# SCH_555-Circut_2025-10-18.net
KiCad netlist of a schematic drawn in EasyEDA
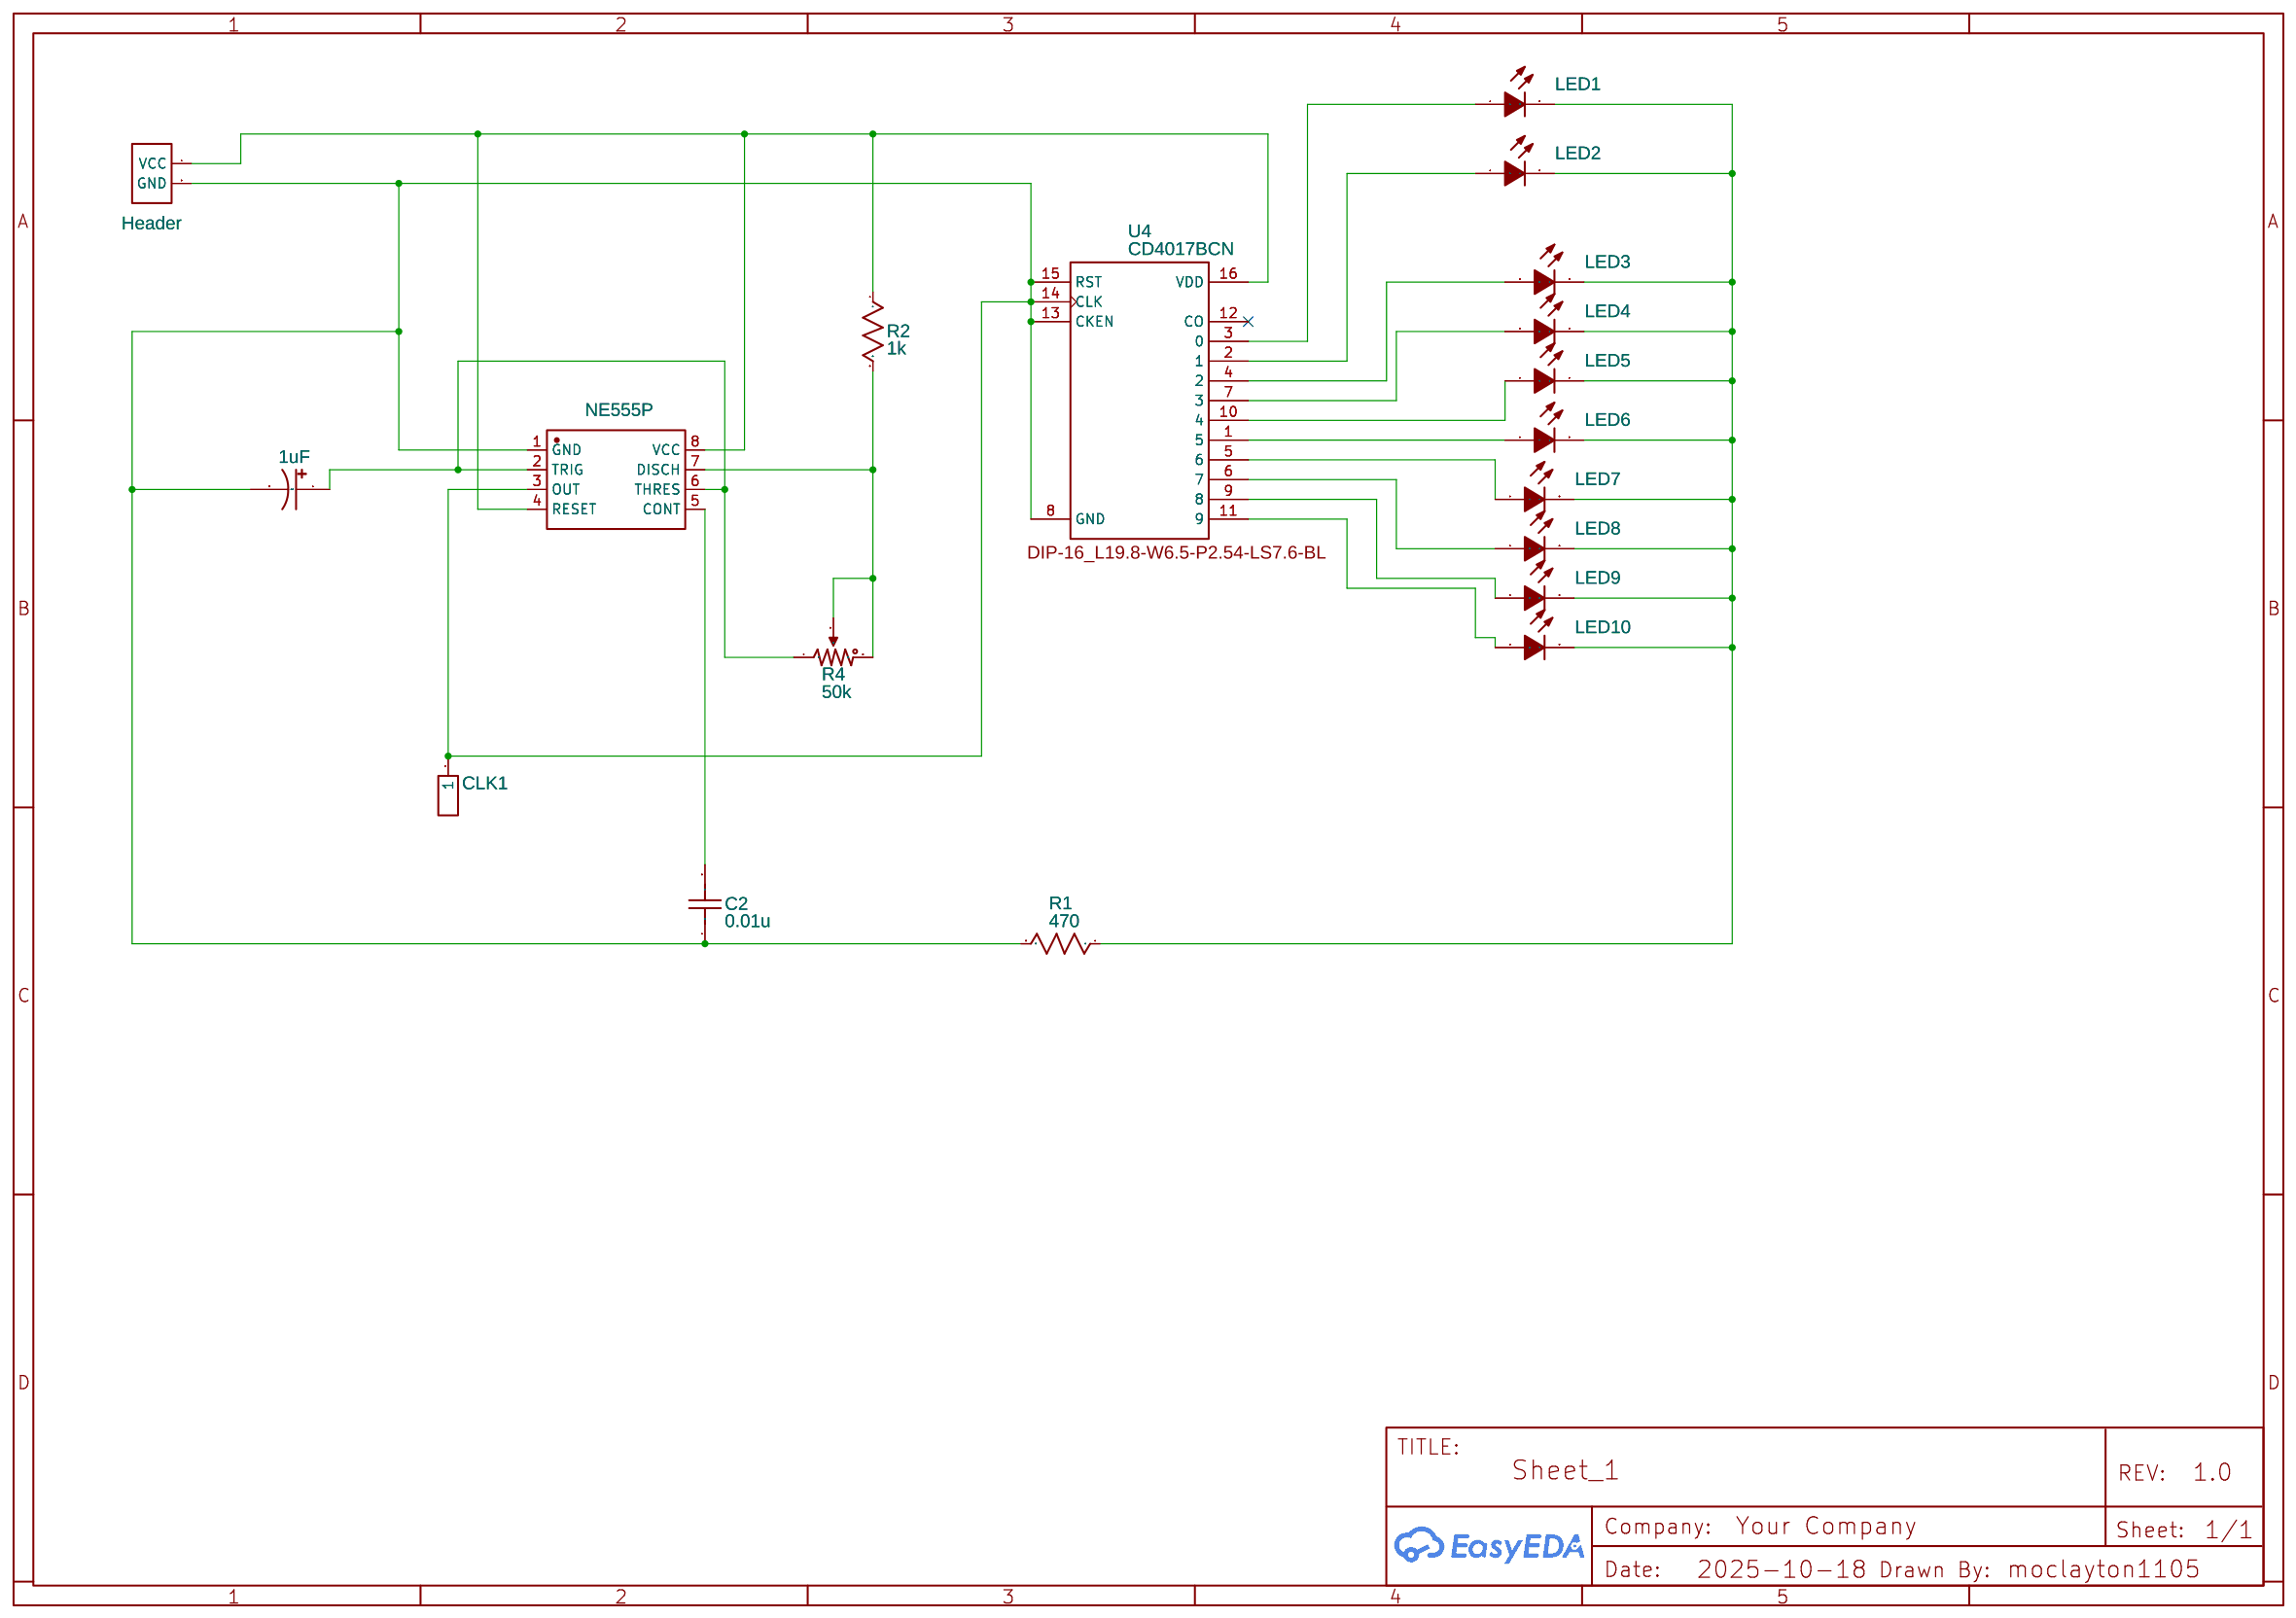
[diagram p0: schematic sheet]

(export (version "E")
  (design (tool "Eeschema 10.0.6"))
  (components
    (comp (ref "C1")
      (value "1uF")
      (fields (field (name "Manufacturer Part") "UVZ1H010MDD") (field (name "Manufacturer") "Nichicon(尼吉康)"))
      (libsource (lib "") (part "UVZ1H010MDD"))
    )
    (comp (ref "C2") (value "0.01u") (libsource (lib "") (part "C_0603_US")))
    (comp (ref "CLK1")
      (value "C81276")
      (fields
        (field (name "Manufacturer Part") "2.54-1*1P针")
        (field (name "Manufacturer") "BOOMELE(Boom Precision Elec)")
      )
      (libsource (lib "") (part "Header-Male-2.54_1x1"))
    )
    (comp (ref "H1") (value "Header") (libsource (lib "") (part "HEADER-FEMALE-2.54_1X2")))
    (comp (ref "LED1") (value "LED_5MM") (libsource (lib "") (part "LED_5MM")))
    (comp (ref "LED2") (value "LED_5MM") (libsource (lib "") (part "LED_5MM")))
    (comp (ref "LED3") (value "LED_5MM") (libsource (lib "") (part "LED_5MM")))
    (comp (ref "LED4") (value "LED_5MM") (libsource (lib "") (part "LED_5MM")))
    (comp (ref "LED5") (value "LED_5MM") (libsource (lib "") (part "LED_5MM")))
    (comp (ref "LED6") (value "LED_5MM") (libsource (lib "") (part "LED_5MM")))
    (comp (ref "LED7") (value "LED_5MM") (libsource (lib "") (part "LED_5MM")))
    (comp (ref "LED8") (value "LED_5MM") (libsource (lib "") (part "LED_5MM")))
    (comp (ref "LED9") (value "LED_5MM") (libsource (lib "") (part "LED_5MM")))
    (comp (ref "LED10") (value "LED_5MM") (libsource (lib "") (part "LED_5MM")))
    (comp (ref "R1")
      (value "470")
      (fields (field (name "Manufacturer Part") "?"))
      (libsource (lib "") (part "Resistor"))
    )
    (comp (ref "R2")
      (value "1k")
      (fields (field (name "Manufacturer Part") "?"))
      (libsource (lib "") (part "Resistor_1"))
    )
    (comp (ref "R4")
      (value "50k")
      (fields (field (name "Manufacturer Part") "?"))
      (libsource (lib "") (part "Potentiometer"))
    )
    (comp (ref "U2")
      (value "NE555P")
      (fields (field (name "Manufacturer") "TI(德州仪器)"))
      (libsource (lib "") (part "NE555P"))
    )
    (comp (ref "U4") (value "CD4017BCN") (libsource (lib "") (part "CD4017BCN")))
  )
  (nets
    (net (code "1") (name "Net-(H1-GND)") (class "Default")
      (node (ref "C1") (pin "2") (pinfunction "2_2") (pintype "unspecified"))
      (node (ref "C2") (pin "1") (pinfunction "1_1") (pintype "unspecified"))
      (node (ref "CLK1") (pin "1") (pinfunction "1_1") (pintype "unspecified"))
      (node (ref "H1") (pin "2") (pinfunction "GND_2") (pintype "unspecified"))
      (node (ref "R1") (pin "2") (pinfunction "2_2") (pintype "unspecified"))
      (node (ref "U2") (pin "1") (pinfunction "GND_1") (pintype "unspecified"))
      (node (ref "U2") (pin "3") (pinfunction "OUT_3") (pintype "unspecified"))
      (node (ref "U4") (pin "13") (pinfunction "CKEN_13") (pintype "unspecified"))
      (node (ref "U4") (pin "14") (pinfunction "CLK_14") (pintype "unspecified"))
      (node (ref "U4") (pin "15") (pinfunction "RST_15") (pintype "unspecified"))
      (node (ref "U4") (pin "8") (pinfunction "GND_8") (pintype "passive"))
    )
    (net (code "2") (name "Net-(H1-VCC)") (class "Default")
      (node (ref "H1") (pin "1") (pinfunction "VCC_1") (pintype "unspecified"))
      (node (ref "R2") (pin "1") (pinfunction "1_1") (pintype "unspecified"))
      (node (ref "U2") (pin "4") (pinfunction "RESET_4") (pintype "unspecified"))
      (node (ref "U2") (pin "8") (pinfunction "VCC_8") (pintype "unspecified"))
      (node (ref "U4") (pin "16") (pinfunction "VDD_16") (pintype "passive"))
    )
    (net (code "3") (name "Net-(LED1-A)") (class "Default")
      (node (ref "LED1") (pin "1") (pinfunction "A_1") (pintype "input"))
      (node (ref "U4") (pin "3") (pinfunction "0_3") (pintype "output"))
    )
    (net (code "4") (name "Net-(LED1-K)") (class "Default")
      (node (ref "LED1") (pin "2") (pinfunction "K_2") (pintype "input"))
      (node (ref "LED10") (pin "2") (pinfunction "K_2") (pintype "input"))
      (node (ref "LED2") (pin "2") (pinfunction "K_2") (pintype "input"))
      (node (ref "LED3") (pin "2") (pinfunction "K_2") (pintype "input"))
      (node (ref "LED4") (pin "2") (pinfunction "K_2") (pintype "input"))
      (node (ref "LED5") (pin "2") (pinfunction "K_2") (pintype "input"))
      (node (ref "LED6") (pin "2") (pinfunction "K_2") (pintype "input"))
      (node (ref "LED7") (pin "2") (pinfunction "K_2") (pintype "input"))
      (node (ref "LED8") (pin "2") (pinfunction "K_2") (pintype "input"))
      (node (ref "LED9") (pin "2") (pinfunction "K_2") (pintype "input"))
      (node (ref "R1") (pin "1") (pinfunction "1_1") (pintype "unspecified"))
    )
    (net (code "5") (name "Net-(LED2-A)") (class "Default")
      (node (ref "LED2") (pin "1") (pinfunction "A_1") (pintype "input"))
      (node (ref "U4") (pin "2") (pinfunction "1_2") (pintype "output"))
    )
    (net (code "6") (name "Net-(LED3-A)") (class "Default")
      (node (ref "LED3") (pin "1") (pinfunction "A_1") (pintype "input"))
      (node (ref "U4") (pin "4") (pinfunction "2_4") (pintype "output"))
    )
    (net (code "7") (name "Net-(LED4-A)") (class "Default")
      (node (ref "LED4") (pin "1") (pinfunction "A_1") (pintype "input"))
      (node (ref "U4") (pin "7") (pinfunction "3_7") (pintype "output"))
    )
    (net (code "8") (name "Net-(LED5-A)") (class "Default")
      (node (ref "LED5") (pin "1") (pinfunction "A_1") (pintype "input"))
      (node (ref "U4") (pin "10") (pinfunction "4_10") (pintype "output"))
    )
    (net (code "9") (name "Net-(LED6-A)") (class "Default")
      (node (ref "LED6") (pin "1") (pinfunction "A_1") (pintype "input"))
      (node (ref "U4") (pin "1") (pinfunction "5_1") (pintype "output"))
    )
    (net (code "10") (name "Net-(LED7-A)") (class "Default")
      (node (ref "LED7") (pin "1") (pinfunction "A_1") (pintype "input"))
      (node (ref "U4") (pin "5") (pinfunction "6_5") (pintype "output"))
    )
    (net (code "11") (name "Net-(LED8-A)") (class "Default")
      (node (ref "LED8") (pin "1") (pinfunction "A_1") (pintype "input"))
      (node (ref "U4") (pin "6") (pinfunction "7_6") (pintype "output"))
    )
    (net (code "12") (name "Net-(LED9-A)") (class "Default")
      (node (ref "LED9") (pin "1") (pinfunction "A_1") (pintype "input"))
      (node (ref "U4") (pin "9") (pinfunction "8_9") (pintype "output"))
    )
    (net (code "13") (name "Net-(LED10-A)") (class "Default")
      (node (ref "LED10") (pin "1") (pinfunction "A_1") (pintype "input"))
      (node (ref "U4") (pin "11") (pinfunction "9_11") (pintype "output"))
    )
    (net (code "14") (name "Net-(R4-2)") (class "Default")
      (node (ref "R2") (pin "2") (pinfunction "2_2") (pintype "unspecified"))
      (node (ref "R4") (pin "2") (pinfunction "3_2") (pintype "unspecified"))
      (node (ref "R4") (pin "3") (pinfunction "2_3") (pintype "unspecified"))
      (node (ref "U2") (pin "7") (pinfunction "DISCH_7") (pintype "unspecified"))
    )
    (net (code "15") (name "Net-(U2-CONT)") (class "Default")
      (node (ref "C2") (pin "2") (pinfunction "2_2") (pintype "unspecified"))
      (node (ref "U2") (pin "5") (pinfunction "CONT_5") (pintype "unspecified"))
    )
    (net (code "16") (name "Net-(U2-THRES)") (class "Default")
      (node (ref "C1") (pin "1") (pinfunction "1_1") (pintype "unspecified"))
      (node (ref "R4") (pin "1") (pinfunction "1_1") (pintype "unspecified"))
      (node (ref "U2") (pin "2") (pinfunction "TRIG_2") (pintype "unspecified"))
      (node (ref "U2") (pin "6") (pinfunction "THRES_6") (pintype "unspecified"))
    )
    (net (code "17") (name "unconnected-(U4-CO-Pad12)") (class "Default")
      (node (ref "U4") (pin "12") (pinfunction "CO_12") (pintype "output+no_connect"))
    )
  )
)
